# scheme.net
KiCad netlist of a schematic drawn in Altium Designer
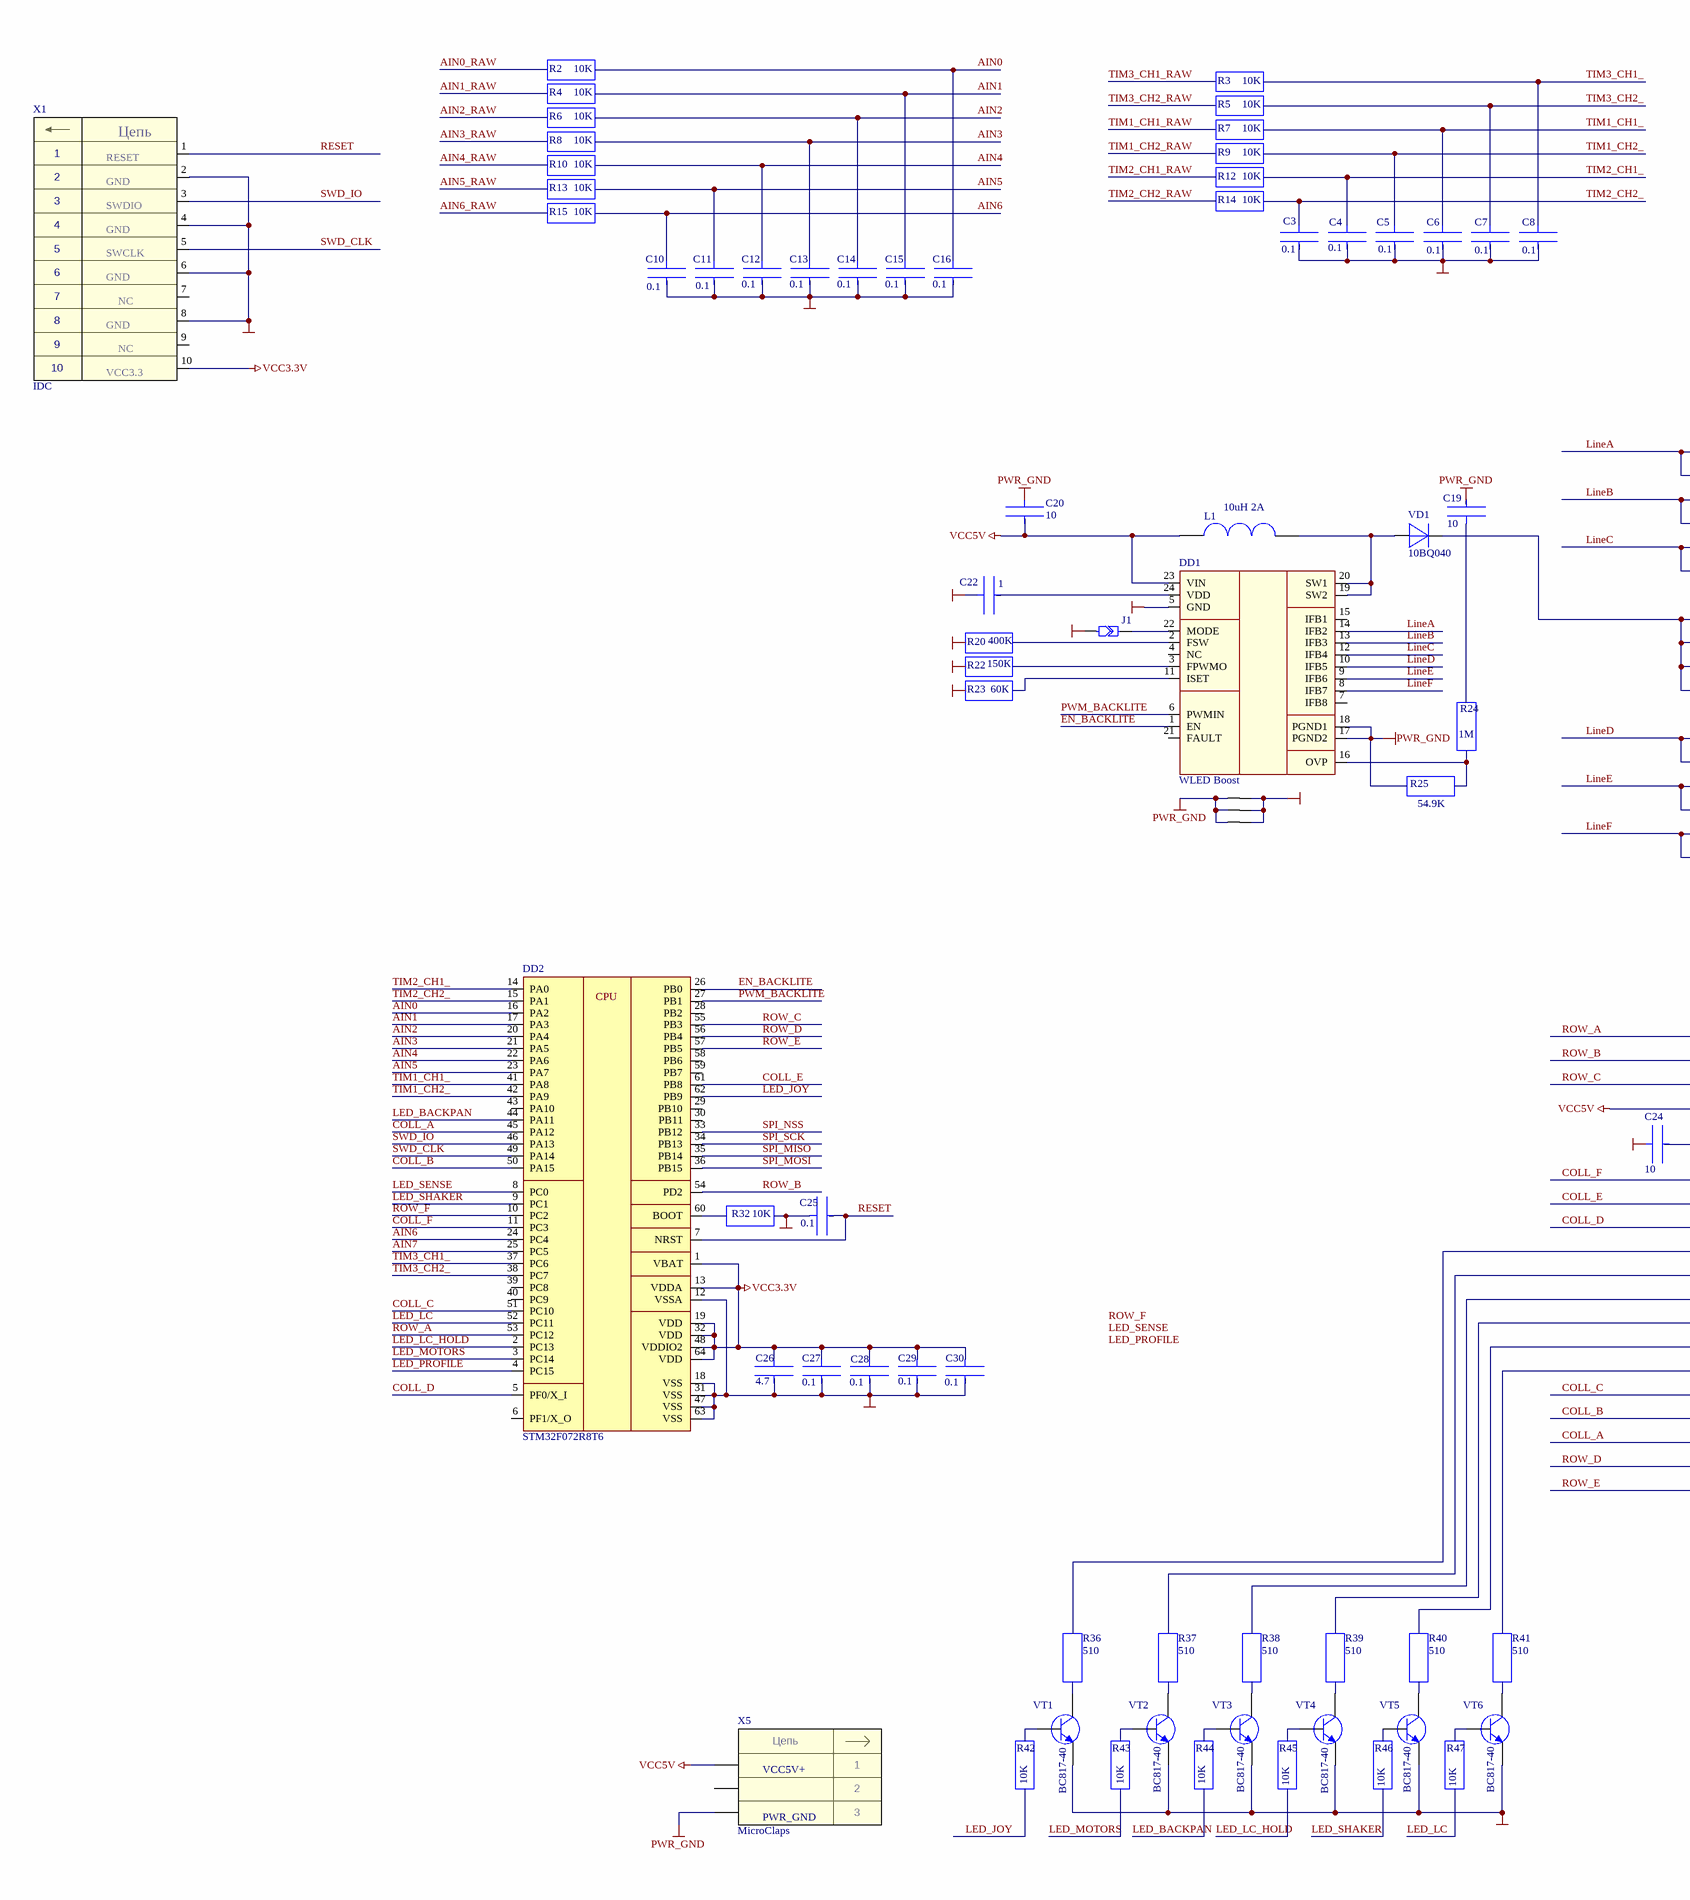
[diagram p0: scheme.SchDoc, left]
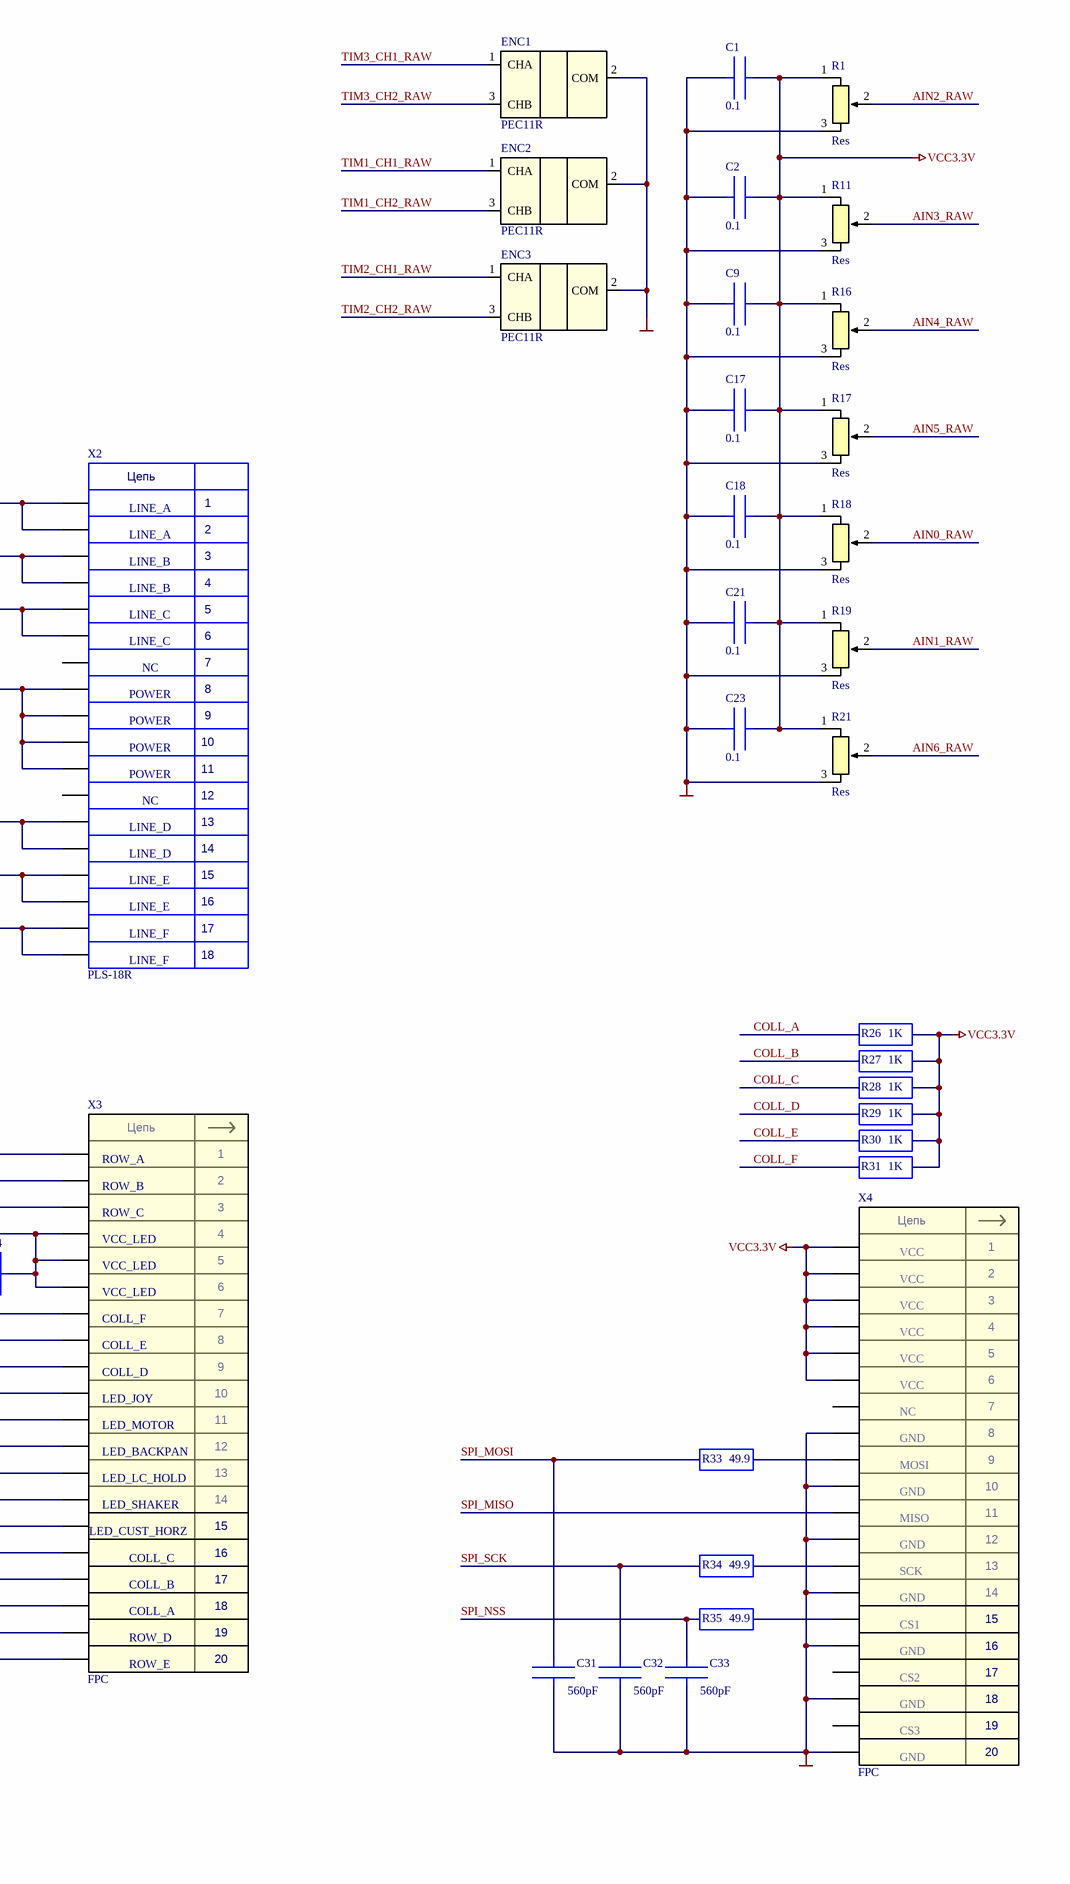
[diagram p1: scheme.SchDoc, right]

(export (version "E")
  (design (tool "Eeschema 10.0.6"))
  (components
    (comp (ref "1")
      (value "Wire Bridge")
      (footprint "Bridge 1.2mm")
      (libsource (lib "DiscreteDevicesCommon") (part "Wire Bridge"))
    )
    (comp (ref "2")
      (value "Wire Bridge")
      (footprint "Bridge 1.2mm")
      (libsource (lib "DiscreteDevicesCommon") (part "Wire Bridge"))
    )
    (comp (ref "3")
      (value "Wire Bridge")
      (footprint "Bridge 1.2mm")
      (libsource (lib "DiscreteDevicesCommon") (part "Wire Bridge"))
    )
    (comp (ref "C1")
      (value "0.1")
      (footprint "C0402")
      (description "Capacitor")
      (fields (field (name "VOLTAGE") "16") (field (name "Comment") "Cap"))
      (libsource (lib "DiscreteDevicesCommon") (part "Cap"))
    )
    (comp (ref "C2")
      (value "0.1")
      (footprint "C0402")
      (description "Capacitor")
      (fields (field (name "VOLTAGE") "16") (field (name "Comment") "Cap"))
      (libsource (lib "DiscreteDevicesCommon") (part "Cap"))
    )
    (comp (ref "C3")
      (value "0.1")
      (footprint "C0402")
      (description "Capacitor")
      (fields (field (name "VOLTAGE") "16") (field (name "Comment") "Cap"))
      (libsource (lib "DiscreteDevicesCommon") (part "Cap"))
    )
    (comp (ref "C4")
      (value "0.1")
      (footprint "C0402")
      (description "Capacitor")
      (fields (field (name "VOLTAGE") "16") (field (name "Comment") "Cap"))
      (libsource (lib "DiscreteDevicesCommon") (part "Cap"))
    )
    (comp (ref "C5")
      (value "0.1")
      (footprint "C0402")
      (description "Capacitor")
      (fields (field (name "VOLTAGE") "16") (field (name "Comment") "Cap"))
      (libsource (lib "DiscreteDevicesCommon") (part "Cap"))
    )
    (comp (ref "C6")
      (value "0.1")
      (footprint "C0402")
      (description "Capacitor")
      (fields (field (name "VOLTAGE") "16") (field (name "Comment") "Cap"))
      (libsource (lib "DiscreteDevicesCommon") (part "Cap"))
    )
    (comp (ref "C7")
      (value "0.1")
      (footprint "C0402")
      (description "Capacitor")
      (fields (field (name "VOLTAGE") "16") (field (name "Comment") "Cap"))
      (libsource (lib "DiscreteDevicesCommon") (part "Cap"))
    )
    (comp (ref "C8")
      (value "0.1")
      (footprint "C0402")
      (description "Capacitor")
      (fields (field (name "VOLTAGE") "16") (field (name "Comment") "Cap"))
      (libsource (lib "DiscreteDevicesCommon") (part "Cap"))
    )
    (comp (ref "C9")
      (value "0.1")
      (footprint "C0402")
      (description "Capacitor")
      (fields (field (name "VOLTAGE") "16") (field (name "Comment") "Cap"))
      (libsource (lib "DiscreteDevicesCommon") (part "Cap"))
    )
    (comp (ref "C10")
      (value "0.1")
      (footprint "C0402")
      (description "Capacitor")
      (fields (field (name "VOLTAGE") "16") (field (name "Comment") "Cap"))
      (libsource (lib "DiscreteDevicesCommon") (part "Cap"))
    )
    (comp (ref "C11")
      (value "0.1")
      (footprint "C0402")
      (description "Capacitor")
      (fields (field (name "VOLTAGE") "16") (field (name "Comment") "Cap"))
      (libsource (lib "DiscreteDevicesCommon") (part "Cap"))
    )
    (comp (ref "C12")
      (value "0.1")
      (footprint "C0402")
      (description "Capacitor")
      (fields (field (name "VOLTAGE") "16") (field (name "Comment") "Cap"))
      (libsource (lib "DiscreteDevicesCommon") (part "Cap"))
    )
    (comp (ref "C13")
      (value "0.1")
      (footprint "C0402")
      (description "Capacitor")
      (fields (field (name "VOLTAGE") "16") (field (name "Comment") "Cap"))
      (libsource (lib "DiscreteDevicesCommon") (part "Cap"))
    )
    (comp (ref "C14")
      (value "0.1")
      (footprint "C0402")
      (description "Capacitor")
      (fields (field (name "VOLTAGE") "16") (field (name "Comment") "Cap"))
      (libsource (lib "DiscreteDevicesCommon") (part "Cap"))
    )
    (comp (ref "C15")
      (value "0.1")
      (footprint "C0402")
      (description "Capacitor")
      (fields (field (name "VOLTAGE") "16") (field (name "Comment") "Cap"))
      (libsource (lib "DiscreteDevicesCommon") (part "Cap"))
    )
    (comp (ref "C16")
      (value "0.1")
      (footprint "C0402")
      (description "Capacitor")
      (fields (field (name "VOLTAGE") "16") (field (name "Comment") "Cap"))
      (libsource (lib "DiscreteDevicesCommon") (part "Cap"))
    )
    (comp (ref "C17")
      (value "0.1")
      (footprint "C0402")
      (description "Capacitor")
      (fields (field (name "VOLTAGE") "16") (field (name "Comment") "Cap"))
      (libsource (lib "DiscreteDevicesCommon") (part "Cap"))
    )
    (comp (ref "C18")
      (value "0.1")
      (footprint "C0402")
      (description "Capacitor")
      (fields (field (name "VOLTAGE") "16") (field (name "Comment") "Cap"))
      (libsource (lib "DiscreteDevicesCommon") (part "Cap"))
    )
    (comp (ref "C19")
      (value "10")
      (footprint "C1206")
      (description "Capacitor")
      (fields (field (name "VOLTAGE") "25") (field (name "Comment") "Cap"))
      (libsource (lib "DiscreteDevicesCommon") (part "Cap"))
    )
    (comp (ref "C20")
      (value "10")
      (footprint "C1206")
      (description "Capacitor")
      (fields (field (name "VOLTAGE") "25") (field (name "Comment") "Cap"))
      (libsource (lib "DiscreteDevicesCommon") (part "Cap"))
    )
    (comp (ref "C21")
      (value "0.1")
      (footprint "C0402")
      (description "Capacitor")
      (fields (field (name "VOLTAGE") "16") (field (name "Comment") "Cap"))
      (libsource (lib "DiscreteDevicesCommon") (part "Cap"))
    )
    (comp (ref "C22")
      (value "1")
      (footprint "C0603")
      (description "Capacitor")
      (fields (field (name "VOLTAGE") "6.3") (field (name "Comment") "Cap"))
      (libsource (lib "DiscreteDevicesCommon") (part "Cap"))
    )
    (comp (ref "C23")
      (value "0.1")
      (footprint "C0402")
      (description "Capacitor")
      (fields (field (name "VOLTAGE") "16") (field (name "Comment") "Cap"))
      (libsource (lib "DiscreteDevicesCommon") (part "Cap"))
    )
    (comp (ref "C24")
      (value "10")
      (footprint "C1206")
      (description "Capacitor")
      (fields (field (name "VOLTAGE") "25") (field (name "Comment") "Cap"))
      (libsource (lib "DiscreteDevicesCommon") (part "Cap"))
    )
    (comp (ref "C25")
      (value "0.1")
      (footprint "C0402")
      (description "Capacitor")
      (fields (field (name "VOLTAGE") "16") (field (name "Comment") "Cap"))
      (libsource (lib "DiscreteDevicesCommon") (part "Cap"))
    )
    (comp (ref "C26")
      (value "4.7")
      (footprint "C0402")
      (description "Capacitor")
      (fields (field (name "VOLTAGE") "6.3") (field (name "Comment") "Cap"))
      (libsource (lib "DiscreteDevicesCommon") (part "Cap"))
    )
    (comp (ref "C27")
      (value "0.1")
      (footprint "C0402")
      (description "Capacitor")
      (fields (field (name "VOLTAGE") "16") (field (name "Comment") "Cap"))
      (libsource (lib "DiscreteDevicesCommon") (part "Cap"))
    )
    (comp (ref "C28")
      (value "0.1")
      (footprint "C0402")
      (description "Capacitor")
      (fields (field (name "VOLTAGE") "16") (field (name "Comment") "Cap"))
      (libsource (lib "DiscreteDevicesCommon") (part "Cap"))
    )
    (comp (ref "C29")
      (value "0.1")
      (footprint "C0402")
      (description "Capacitor")
      (fields (field (name "VOLTAGE") "16") (field (name "Comment") "Cap"))
      (libsource (lib "DiscreteDevicesCommon") (part "Cap"))
    )
    (comp (ref "C30")
      (value "0.1")
      (footprint "C0402")
      (description "Capacitor")
      (fields (field (name "VOLTAGE") "16") (field (name "Comment") "Cap"))
      (libsource (lib "DiscreteDevicesCommon") (part "Cap"))
    )
    (comp (ref "C31")
      (value "560pF")
      (footprint "C0402")
      (description "Capacitor")
      (fields (field (name "VOLTAGE") "16") (field (name "Comment") "Cap"))
      (libsource (lib "DiscreteDevicesCommon") (part "Cap"))
    )
    (comp (ref "C32")
      (value "560pF")
      (footprint "C0402")
      (description "Capacitor")
      (fields (field (name "VOLTAGE") "16") (field (name "Comment") "Cap"))
      (libsource (lib "DiscreteDevicesCommon") (part "Cap"))
    )
    (comp (ref "C33")
      (value "560pF")
      (footprint "C0402")
      (description "Capacitor")
      (fields (field (name "VOLTAGE") "16") (field (name "Comment") "Cap"))
      (libsource (lib "DiscreteDevicesCommon") (part "Cap"))
    )
    (comp (ref "DD1")
      (value "WLED Boost")
      (footprint "WQFN-24")
      (libsource (lib "ChipsCommon") (part "TPS61185"))
    )
    (comp (ref "DD2")
      (value "STM32F072Rx")
      (footprint "LQFP64_M")
      (fields (field (name "TYPE") "STM32F072R8T6"))
      (libsource (lib "ChipsCommon") (part "STM32F072Rx"))
    )
    (comp (ref "ENC1")
      (value "PEC11R")
      (footprint "PEC11R")
      (description "ENCODER")
      (libsource (lib "DiscreteDevicesCommon") (part "PEC11R ENCODER"))
    )
    (comp (ref "ENC2")
      (value "PEC11R")
      (footprint "PEC11R")
      (description "ENCODER")
      (libsource (lib "DiscreteDevicesCommon") (part "PEC11R ENCODER"))
    )
    (comp (ref "ENC3")
      (value "PEC11R")
      (footprint "PEC11R")
      (description "ENCODER")
      (libsource (lib "DiscreteDevicesCommon") (part "PEC11R ENCODER"))
    )
    (comp (ref "J1")
      (value "JumperB")
      (footprint "SM/JUMPER_SHORT")
      (description "Jumper on Board")
      (libsource (lib "ConnectorsCommon") (part "JumperB"))
    )
    (comp (ref "L1")
      (value "10uH 2A")
      (footprint "SDR0805")
      (description "Inductor")
      (fields (field (name "Comment") "IND2"))
      (libsource (lib "DiscreteDevicesCommon") (part "IND2"))
    )
    (comp (ref "R1")
      (value "Res")
      (footprint "P16NP_16mm")
      (description "Potenciometr")
      (libsource (lib "DiscreteDevicesCommon") (part "P16A Res"))
    )
    (comp (ref "R2")
      (value "10K")
      (footprint "R0402")
      (description "Resistor")
      (fields (field (name "Comment") "Res"))
      (libsource (lib "") (part "Res_1"))
    )
    (comp (ref "R3")
      (value "10K")
      (footprint "R0402")
      (description "Resistor")
      (fields (field (name "Comment") "Res"))
      (libsource (lib "") (part "Res_1"))
    )
    (comp (ref "R4")
      (value "10K")
      (footprint "R0402")
      (description "Resistor")
      (fields (field (name "Comment") "Res"))
      (libsource (lib "") (part "Res_1"))
    )
    (comp (ref "R5")
      (value "10K")
      (footprint "R0402")
      (description "Resistor")
      (fields (field (name "Comment") "Res"))
      (libsource (lib "") (part "Res_1"))
    )
    (comp (ref "R6")
      (value "10K")
      (footprint "R0402")
      (description "Resistor")
      (fields (field (name "Comment") "Res"))
      (libsource (lib "") (part "Res_1"))
    )
    (comp (ref "R7")
      (value "10K")
      (footprint "R0402")
      (description "Resistor")
      (fields (field (name "Comment") "Res"))
      (libsource (lib "") (part "Res_1"))
    )
    (comp (ref "R8")
      (value "10K")
      (footprint "R0402")
      (description "Resistor")
      (fields (field (name "Comment") "Res"))
      (libsource (lib "") (part "Res_1"))
    )
    (comp (ref "R9")
      (value "10K")
      (footprint "R0402")
      (description "Resistor")
      (fields (field (name "Comment") "Res"))
      (libsource (lib "") (part "Res_1"))
    )
    (comp (ref "R10")
      (value "10K")
      (footprint "R0402")
      (description "Resistor")
      (fields (field (name "Comment") "Res"))
      (libsource (lib "") (part "Res_1"))
    )
    (comp (ref "R11")
      (value "Res")
      (footprint "P16NP_16mm")
      (description "Potenciometr")
      (libsource (lib "DiscreteDevicesCommon") (part "P16A Res"))
    )
    (comp (ref "R12")
      (value "10K")
      (footprint "R0402")
      (description "Resistor")
      (fields (field (name "Comment") "Res"))
      (libsource (lib "") (part "Res_1"))
    )
    (comp (ref "R13")
      (value "10K")
      (footprint "R0402")
      (description "Resistor")
      (fields (field (name "Comment") "Res"))
      (libsource (lib "") (part "Res_1"))
    )
    (comp (ref "R14")
      (value "10K")
      (footprint "R0402")
      (description "Resistor")
      (fields (field (name "Comment") "Res"))
      (libsource (lib "") (part "Res_1"))
    )
    (comp (ref "R15")
      (value "10K")
      (footprint "R0402")
      (description "Resistor")
      (fields (field (name "Comment") "Res"))
      (libsource (lib "") (part "Res_1"))
    )
    (comp (ref "R16")
      (value "Res")
      (footprint "P16NP_16mm")
      (description "Potenciometr")
      (libsource (lib "DiscreteDevicesCommon") (part "P16A Res"))
    )
    (comp (ref "R17")
      (value "Res")
      (footprint "P16NP_16mm")
      (description "Potenciometr")
      (libsource (lib "DiscreteDevicesCommon") (part "P16A Res"))
    )
    (comp (ref "R18")
      (value "Res")
      (footprint "P16NP_16mm")
      (description "Potenciometr")
      (libsource (lib "DiscreteDevicesCommon") (part "P16A Res"))
    )
    (comp (ref "R19")
      (value "Res")
      (footprint "P16NP_16mm")
      (description "Potenciometr")
      (libsource (lib "DiscreteDevicesCommon") (part "P16A Res"))
    )
    (comp (ref "R20")
      (value "400K")
      (footprint "R0402")
      (description "Resistor")
      (fields (field (name "Comment") "Res"))
      (libsource (lib "") (part "Res_1"))
    )
    (comp (ref "R21")
      (value "Res")
      (footprint "P16NP_16mm")
      (description "Potenciometr")
      (libsource (lib "DiscreteDevicesCommon") (part "P16A Res"))
    )
    (comp (ref "R22")
      (value "150К")
      (footprint "R0402")
      (description "Resistor")
      (fields (field (name "Comment") "Res"))
      (libsource (lib "") (part "Res_1"))
    )
    (comp (ref "R23")
      (value "60К")
      (footprint "R0402")
      (description "Resistor")
      (fields (field (name "Comment") "Res"))
      (libsource (lib "") (part "Res_1"))
    )
    (comp (ref "R24")
      (value "1M")
      (footprint "R0603")
      (description "Resistor")
      (fields (field (name "Comment") "Res"))
      (libsource (lib "DiscreteDevicesCommon") (part "Res"))
    )
    (comp (ref "R25")
      (value "54.9K")
      (footprint "R0603")
      (description "Resistor")
      (fields (field (name "Comment") "Res"))
      (libsource (lib "") (part "Res_2"))
    )
    (comp (ref "R26")
      (value "1K")
      (footprint "R0402")
      (description "Resistor")
      (fields (field (name "Comment") "Res"))
      (libsource (lib "") (part "Res_1"))
    )
    (comp (ref "R27")
      (value "1K")
      (footprint "R0402")
      (description "Resistor")
      (fields (field (name "Comment") "Res"))
      (libsource (lib "") (part "Res_1"))
    )
    (comp (ref "R28")
      (value "1K")
      (footprint "R0402")
      (description "Resistor")
      (fields (field (name "Comment") "Res"))
      (libsource (lib "") (part "Res_1"))
    )
    (comp (ref "R29")
      (value "1K")
      (footprint "R0402")
      (description "Resistor")
      (fields (field (name "Comment") "Res"))
      (libsource (lib "") (part "Res_1"))
    )
    (comp (ref "R30")
      (value "1K")
      (footprint "R0402")
      (description "Resistor")
      (fields (field (name "Comment") "Res"))
      (libsource (lib "") (part "Res_1"))
    )
    (comp (ref "R31")
      (value "1K")
      (footprint "R0402")
      (description "Resistor")
      (fields (field (name "Comment") "Res"))
      (libsource (lib "") (part "Res_1"))
    )
    (comp (ref "R32")
      (value "10K")
      (footprint "R0402")
      (description "Resistor")
      (fields (field (name "Comment") "Res"))
      (libsource (lib "") (part "Res_1"))
    )
    (comp (ref "R33")
      (value "49.9")
      (footprint "R0402")
      (description "Resistor")
      (fields (field (name "Comment") "Res"))
      (libsource (lib "") (part "Res_1"))
    )
    (comp (ref "R34")
      (value "49.9")
      (footprint "R0402")
      (description "Resistor")
      (fields (field (name "Comment") "Res"))
      (libsource (lib "") (part "Res_1"))
    )
    (comp (ref "R35")
      (value "49.9")
      (footprint "R0402")
      (description "Resistor")
      (fields (field (name "Comment") "Res"))
      (libsource (lib "") (part "Res_1"))
    )
    (comp (ref "R36")
      (value "510")
      (footprint "R0402")
      (description "Resistor")
      (fields (field (name "Comment") "Res"))
      (libsource (lib "DiscreteDevicesCommon") (part "Res"))
    )
    (comp (ref "R37")
      (value "510")
      (footprint "R0402")
      (description "Resistor")
      (fields (field (name "Comment") "Res"))
      (libsource (lib "DiscreteDevicesCommon") (part "Res"))
    )
    (comp (ref "R38")
      (value "510")
      (footprint "R0402")
      (description "Resistor")
      (fields (field (name "Comment") "Res"))
      (libsource (lib "DiscreteDevicesCommon") (part "Res"))
    )
    (comp (ref "R39")
      (value "510")
      (footprint "R0402")
      (description "Resistor")
      (fields (field (name "Comment") "Res"))
      (libsource (lib "DiscreteDevicesCommon") (part "Res"))
    )
    (comp (ref "R40")
      (value "510")
      (footprint "R0402")
      (description "Resistor")
      (fields (field (name "Comment") "Res"))
      (libsource (lib "DiscreteDevicesCommon") (part "Res"))
    )
    (comp (ref "R41")
      (value "510")
      (footprint "R0402")
      (description "Resistor")
      (fields (field (name "Comment") "Res"))
      (libsource (lib "DiscreteDevicesCommon") (part "Res"))
    )
    (comp (ref "R42")
      (value "10K")
      (footprint "R0402")
      (description "Resistor")
      (fields (field (name "Comment") "Res"))
      (libsource (lib "DiscreteDevicesCommon") (part "Res"))
    )
    (comp (ref "R43")
      (value "10K")
      (footprint "R0402")
      (description "Resistor")
      (fields (field (name "Comment") "Res"))
      (libsource (lib "DiscreteDevicesCommon") (part "Res"))
    )
    (comp (ref "R44")
      (value "10K")
      (footprint "R0402")
      (description "Resistor")
      (fields (field (name "Comment") "Res"))
      (libsource (lib "DiscreteDevicesCommon") (part "Res"))
    )
    (comp (ref "R45")
      (value "10K")
      (footprint "R0402")
      (description "Resistor")
      (fields (field (name "Comment") "Res"))
      (libsource (lib "DiscreteDevicesCommon") (part "Res"))
    )
    (comp (ref "R46")
      (value "10K")
      (footprint "R0402")
      (description "Resistor")
      (fields (field (name "Comment") "Res"))
      (libsource (lib "DiscreteDevicesCommon") (part "Res"))
    )
    (comp (ref "R47")
      (value "10K")
      (footprint "R0402")
      (description "Resistor")
      (fields (field (name "Comment") "Res"))
      (libsource (lib "DiscreteDevicesCommon") (part "Res"))
    )
    (comp (ref "VD1")
      (value "Diode")
      (footprint "DI-SMB")
      (fields (field (name "TYPE") "10BQ040"))
      (libsource (lib "DiscreteDevicesCommon") (part "Diode"))
    )
    (comp (ref "VT1")
      (value "Transistor NPN")
      (footprint "SOT23-3L")
      (description "NPN transistor")
      (fields (field (name "TYPE") "BC817-40"))
      (libsource (lib "DiscreteDevicesCommon") (part "Trans NPN"))
    )
    (comp (ref "VT2")
      (value "Transistor NPN")
      (footprint "SOT23-3L")
      (description "NPN transistor")
      (fields (field (name "TYPE") "BC817-40"))
      (libsource (lib "DiscreteDevicesCommon") (part "Trans NPN"))
    )
    (comp (ref "VT3")
      (value "Transistor NPN")
      (footprint "SOT23-3L")
      (description "NPN transistor")
      (fields (field (name "TYPE") "BC817-40"))
      (libsource (lib "DiscreteDevicesCommon") (part "Trans NPN"))
    )
    (comp (ref "VT4")
      (value "Transistor NPN")
      (footprint "SOT23-3L")
      (description "NPN transistor")
      (fields (field (name "TYPE") "BC817-40"))
      (libsource (lib "DiscreteDevicesCommon") (part "Trans NPN"))
    )
    (comp (ref "VT5")
      (value "Transistor NPN")
      (footprint "SOT23-3L")
      (description "NPN transistor")
      (fields (field (name "TYPE") "BC817-40"))
      (libsource (lib "DiscreteDevicesCommon") (part "Trans NPN"))
    )
    (comp (ref "VT6")
      (value "Transistor NPN")
      (footprint "SOT23-3L")
      (description "NPN transistor")
      (fields (field (name "TYPE") "BC817-40"))
      (libsource (lib "DiscreteDevicesCommon") (part "Trans NPN"))
    )
    (comp (ref "X1")
      (value "IDC")
      (footprint "IDC2-10MS-SMD")
      (description "IDC 2mm 10 pin")
      (libsource (lib "ConnectorsCommon") (part "IDC2-10"))
    )
    (comp (ref "X2")
      (value "18-pin Out")
      (footprint "PLS-18R")
      (description "18-pin Out Connector")
      (fields (field (name "TYPE") "PLS-18R"))
      (libsource (lib "ConnectorsCommon") (part "18-pin Out"))
    )
    (comp (ref "X3")
      (value "FPC")
      (footprint "FPC-20 TE 2-84953-0")
      (description "FPC 20pin 1mm")
      (libsource (lib "ConnectorsCommon") (part "FPC-20pin 1mm"))
    )
    (comp (ref "X4")
      (value "FPC")
      (footprint "FPC-20 TE 2-1734592-0")
      (description "FPC 20pin 0.5mm")
      (libsource (lib "ConnectorsCommon") (part "FPC-20pin 0.5mm"))
    )
    (comp (ref "X5")
      (value "MicroClaps")
      (footprint "MicroClaspSingle - 3Pin")
      (description "MicroClapsConnector 3Pin SingleLine")
      (libsource (lib "ConnectorsCommon") (part "MicroClapsSingle-3"))
    )
  )
  (nets
    (net (code "1") (name "/AIN0") (class "Default")
      (node (ref "C16") (pin "1") (pinfunction "1_1") (pintype "passive"))
      (node (ref "DD2") (pin "16") (pinfunction "PA2_16") (pintype "passive"))
      (node (ref "R2") (pin "2") (pinfunction "2_2") (pintype "passive"))
    )
    (net (code "2") (name "/AIN0_RAW") (class "Default")
      (node (ref "R18") (pin "2") (pinfunction "2_2") (pintype "passive"))
      (node (ref "R2") (pin "1") (pinfunction "1_1") (pintype "passive"))
    )
    (net (code "3") (name "/AIN1") (class "Default")
      (node (ref "C15") (pin "1") (pinfunction "1_1") (pintype "passive"))
      (node (ref "DD2") (pin "17") (pinfunction "PA3_17") (pintype "passive"))
      (node (ref "R4") (pin "2") (pinfunction "2_2") (pintype "passive"))
    )
    (net (code "4") (name "/AIN1_RAW") (class "Default")
      (node (ref "R19") (pin "2") (pinfunction "2_2") (pintype "passive"))
      (node (ref "R4") (pin "1") (pinfunction "1_1") (pintype "passive"))
    )
    (net (code "5") (name "/AIN2") (class "Default")
      (node (ref "C14") (pin "1") (pinfunction "1_1") (pintype "passive"))
      (node (ref "DD2") (pin "20") (pinfunction "PA4_20") (pintype "passive"))
      (node (ref "R6") (pin "2") (pinfunction "2_2") (pintype "passive"))
    )
    (net (code "6") (name "/AIN2_RAW") (class "Default")
      (node (ref "R1") (pin "2") (pinfunction "2_2") (pintype "passive"))
      (node (ref "R6") (pin "1") (pinfunction "1_1") (pintype "passive"))
    )
    (net (code "7") (name "/AIN3") (class "Default")
      (node (ref "C13") (pin "1") (pinfunction "1_1") (pintype "passive"))
      (node (ref "DD2") (pin "21") (pinfunction "PA5_21") (pintype "passive"))
      (node (ref "R8") (pin "2") (pinfunction "2_2") (pintype "passive"))
    )
    (net (code "8") (name "/AIN3_RAW") (class "Default")
      (node (ref "R11") (pin "2") (pinfunction "2_2") (pintype "passive"))
      (node (ref "R8") (pin "1") (pinfunction "1_1") (pintype "passive"))
    )
    (net (code "9") (name "/AIN4") (class "Default")
      (node (ref "C12") (pin "1") (pinfunction "1_1") (pintype "passive"))
      (node (ref "DD2") (pin "22") (pinfunction "PA6_22") (pintype "passive"))
      (node (ref "R10") (pin "2") (pinfunction "2_2") (pintype "passive"))
    )
    (net (code "10") (name "/AIN4_RAW") (class "Default")
      (node (ref "R10") (pin "1") (pinfunction "1_1") (pintype "passive"))
      (node (ref "R16") (pin "2") (pinfunction "2_2") (pintype "passive"))
    )
    (net (code "11") (name "/AIN5") (class "Default")
      (node (ref "C11") (pin "1") (pinfunction "1_1") (pintype "passive"))
      (node (ref "DD2") (pin "23") (pinfunction "PA7_23") (pintype "passive"))
      (node (ref "R13") (pin "2") (pinfunction "2_2") (pintype "passive"))
    )
    (net (code "12") (name "/AIN5_RAW") (class "Default")
      (node (ref "R13") (pin "1") (pinfunction "1_1") (pintype "passive"))
      (node (ref "R17") (pin "2") (pinfunction "2_2") (pintype "passive"))
    )
    (net (code "13") (name "/AIN6") (class "Default")
      (node (ref "C10") (pin "1") (pinfunction "1_1") (pintype "passive"))
      (node (ref "DD2") (pin "24") (pinfunction "PC4_24") (pintype "passive"))
      (node (ref "R15") (pin "2") (pinfunction "2_2") (pintype "passive"))
    )
    (net (code "14") (name "/AIN6_RAW") (class "Default")
      (node (ref "R15") (pin "1") (pinfunction "1_1") (pintype "passive"))
      (node (ref "R21") (pin "2") (pinfunction "2_2") (pintype "passive"))
    )
    (net (code "15") (name "/AIN7") (class "Default")
      (node (ref "DD2") (pin "25") (pinfunction "PC5_25") (pintype "passive"))
    )
    (net (code "16") (name "/COLL_A") (class "Default")
      (node (ref "DD2") (pin "45") (pinfunction "PA12_45") (pintype "passive"))
      (node (ref "R26") (pin "1") (pinfunction "1_1") (pintype "passive"))
      (node (ref "X3") (pin "18") (pinfunction "XXX_18") (pintype "passive"))
    )
    (net (code "17") (name "/COLL_B") (class "Default")
      (node (ref "DD2") (pin "50") (pinfunction "PA15_50") (pintype "passive"))
      (node (ref "R27") (pin "1") (pinfunction "1_1") (pintype "passive"))
      (node (ref "X3") (pin "17") (pinfunction "XXX_17") (pintype "passive"))
    )
    (net (code "18") (name "/COLL_C") (class "Default")
      (node (ref "DD2") (pin "51") (pinfunction "PC10_51") (pintype "passive"))
      (node (ref "R28") (pin "1") (pinfunction "1_1") (pintype "passive"))
      (node (ref "X3") (pin "16") (pinfunction "XXX_16") (pintype "passive"))
    )
    (net (code "19") (name "/COLL_D") (class "Default")
      (node (ref "DD2") (pin "5") (pinfunction "PF0/X_I_5") (pintype "passive"))
      (node (ref "R29") (pin "1") (pinfunction "1_1") (pintype "passive"))
      (node (ref "X3") (pin "9") (pinfunction "XXX_9") (pintype "passive"))
    )
    (net (code "20") (name "/COLL_E") (class "Default")
      (node (ref "DD2") (pin "61") (pinfunction "PB8_61") (pintype "passive"))
      (node (ref "R30") (pin "1") (pinfunction "1_1") (pintype "passive"))
      (node (ref "X3") (pin "8") (pinfunction "XXX_8") (pintype "passive"))
    )
    (net (code "21") (name "/COLL_F") (class "Default")
      (node (ref "DD2") (pin "11") (pinfunction "PC3_11") (pintype "passive"))
      (node (ref "R31") (pin "1") (pinfunction "1_1") (pintype "passive"))
      (node (ref "X3") (pin "7") (pinfunction "XXX_7") (pintype "passive"))
    )
    (net (code "22") (name "/EN_BACKLITE") (class "Default")
      (node (ref "DD1") (pin "1") (pinfunction "EN_1") (pintype "passive"))
      (node (ref "DD2") (pin "26") (pinfunction "PB0_26") (pintype "passive"))
    )
    (net (code "23") (name "/LED_BACKPAN") (class "Default")
      (node (ref "DD2") (pin "44") (pinfunction "PA11_44") (pintype "passive"))
      (node (ref "R44") (pin "1") (pinfunction "1_1") (pintype "passive"))
    )
    (net (code "24") (name "/LED_JOY") (class "Default")
      (node (ref "DD2") (pin "62") (pinfunction "PB9_62") (pintype "passive"))
      (node (ref "R42") (pin "1") (pinfunction "1_1") (pintype "passive"))
    )
    (net (code "25") (name "/LED_LC") (class "Default")
      (node (ref "DD2") (pin "52") (pinfunction "PC11_52") (pintype "passive"))
      (node (ref "R47") (pin "1") (pinfunction "1_1") (pintype "passive"))
    )
    (net (code "26") (name "/LED_LC_HOLD") (class "Default")
      (node (ref "DD2") (pin "2") (pinfunction "PC13_2") (pintype "passive"))
      (node (ref "R45") (pin "1") (pinfunction "1_1") (pintype "passive"))
    )
    (net (code "27") (name "/LED_MOTORS") (class "Default")
      (node (ref "DD2") (pin "3") (pinfunction "PC14_3") (pintype "passive"))
      (node (ref "R43") (pin "1") (pinfunction "1_1") (pintype "passive"))
    )
    (net (code "28") (name "/LED_PROFILE") (class "Default")
      (node (ref "DD2") (pin "4") (pinfunction "PC15_4") (pintype "passive"))
    )
    (net (code "29") (name "/LED_SENSE") (class "Default")
      (node (ref "DD2") (pin "8") (pinfunction "PC0_8") (pintype "passive"))
    )
    (net (code "30") (name "/LED_SHAKER") (class "Default")
      (node (ref "DD2") (pin "9") (pinfunction "PC1_9") (pintype "passive"))
      (node (ref "R46") (pin "1") (pinfunction "1_1") (pintype "passive"))
    )
    (net (code "31") (name "/LineA") (class "Default")
      (node (ref "DD1") (pin "14") (pinfunction "IFB2_14") (pintype "passive"))
      (node (ref "X2") (pin "1") (pinfunction "XXX_1") (pintype "passive"))
      (node (ref "X2") (pin "2") (pinfunction "XXX_2") (pintype "passive"))
    )
    (net (code "32") (name "/LineB") (class "Default")
      (node (ref "DD1") (pin "13") (pinfunction "IFB3_13") (pintype "passive"))
      (node (ref "X2") (pin "3") (pinfunction "XXX_3") (pintype "passive"))
      (node (ref "X2") (pin "4") (pinfunction "XXX_4") (pintype "passive"))
    )
    (net (code "33") (name "/LineC") (class "Default")
      (node (ref "DD1") (pin "12") (pinfunction "IFB4_12") (pintype "passive"))
      (node (ref "X2") (pin "5") (pinfunction "XXX_5") (pintype "passive"))
      (node (ref "X2") (pin "6") (pinfunction "XXX_6") (pintype "passive"))
    )
    (net (code "34") (name "/LineD") (class "Default")
      (node (ref "DD1") (pin "10") (pinfunction "IFB5_10") (pintype "passive"))
      (node (ref "X2") (pin "13") (pinfunction "XXX_13") (pintype "passive"))
      (node (ref "X2") (pin "14") (pinfunction "XXX_14") (pintype "passive"))
    )
    (net (code "35") (name "/LineE") (class "Default")
      (node (ref "DD1") (pin "9") (pinfunction "IFB6_9") (pintype "passive"))
      (node (ref "X2") (pin "15") (pinfunction "XXX_15") (pintype "passive"))
      (node (ref "X2") (pin "16") (pinfunction "XXX_16") (pintype "passive"))
    )
    (net (code "36") (name "/LineF") (class "Default")
      (node (ref "DD1") (pin "8") (pinfunction "IFB7_8") (pintype "passive"))
      (node (ref "X2") (pin "17") (pinfunction "XXX_17") (pintype "passive"))
      (node (ref "X2") (pin "18") (pinfunction "XXX_18") (pintype "passive"))
    )
    (net (code "37") (name "/PWM_BACKLITE") (class "Default")
      (node (ref "DD1") (pin "6") (pinfunction "PWMIN_6") (pintype "passive"))
      (node (ref "DD2") (pin "27") (pinfunction "PB1_27") (pintype "passive"))
    )
    (net (code "38") (name "/RESET") (class "Default")
      (node (ref "C25") (pin "2") (pinfunction "2_2") (pintype "passive"))
      (node (ref "DD2") (pin "7") (pinfunction "NRST_7") (pintype "passive"))
      (node (ref "X1") (pin "1") (pinfunction "1_1") (pintype "passive"))
    )
    (net (code "39") (name "/ROW_A") (class "Default")
      (node (ref "DD2") (pin "53") (pinfunction "PC12_53") (pintype "passive"))
      (node (ref "X3") (pin "1") (pinfunction "XXX_1") (pintype "passive"))
    )
    (net (code "40") (name "/ROW_B") (class "Default")
      (node (ref "DD2") (pin "54") (pinfunction "PD2_54") (pintype "passive"))
      (node (ref "X3") (pin "2") (pinfunction "XXX_2") (pintype "passive"))
    )
    (net (code "41") (name "/ROW_C") (class "Default")
      (node (ref "DD2") (pin "55") (pinfunction "PB3_55") (pintype "passive"))
      (node (ref "X3") (pin "3") (pinfunction "XXX_3") (pintype "passive"))
    )
    (net (code "42") (name "/ROW_D") (class "Default")
      (node (ref "DD2") (pin "56") (pinfunction "PB4_56") (pintype "passive"))
      (node (ref "X3") (pin "19") (pinfunction "XXX_19") (pintype "passive"))
    )
    (net (code "43") (name "/ROW_E") (class "Default")
      (node (ref "DD2") (pin "57") (pinfunction "PB5_57") (pintype "passive"))
      (node (ref "X3") (pin "20") (pinfunction "XXX_20") (pintype "passive"))
    )
    (net (code "44") (name "/ROW_F") (class "Default")
      (node (ref "DD2") (pin "10") (pinfunction "PC2_10") (pintype "passive"))
    )
    (net (code "45") (name "/SPI_MISO") (class "Default")
      (node (ref "DD2") (pin "35") (pinfunction "PB14_35") (pintype "passive"))
      (node (ref "X4") (pin "11") (pinfunction "XXX_11") (pintype "passive"))
    )
    (net (code "46") (name "/SPI_MOSI") (class "Default")
      (node (ref "C31") (pin "1") (pinfunction "1_1") (pintype "passive"))
      (node (ref "DD2") (pin "36") (pinfunction "PB15_36") (pintype "passive"))
      (node (ref "R33") (pin "1") (pinfunction "1_1") (pintype "passive"))
    )
    (net (code "47") (name "/SPI_NSS") (class "Default")
      (node (ref "C33") (pin "1") (pinfunction "1_1") (pintype "passive"))
      (node (ref "DD2") (pin "33") (pinfunction "PB12_33") (pintype "passive"))
      (node (ref "R35") (pin "1") (pinfunction "1_1") (pintype "passive"))
    )
    (net (code "48") (name "/SPI_SCK") (class "Default")
      (node (ref "C32") (pin "1") (pinfunction "1_1") (pintype "passive"))
      (node (ref "DD2") (pin "34") (pinfunction "PB13_34") (pintype "passive"))
      (node (ref "R34") (pin "1") (pinfunction "1_1") (pintype "passive"))
    )
    (net (code "49") (name "/SWD_CLK") (class "Default")
      (node (ref "DD2") (pin "49") (pinfunction "PA14_49") (pintype "passive"))
      (node (ref "X1") (pin "5") (pinfunction "5_5") (pintype "passive"))
    )
    (net (code "50") (name "/SWD_IO") (class "Default")
      (node (ref "DD2") (pin "46") (pinfunction "PA13_46") (pintype "passive"))
      (node (ref "X1") (pin "3") (pinfunction "3_3") (pintype "passive"))
    )
    (net (code "51") (name "/TIM1_CH1_") (class "Default")
      (node (ref "C6") (pin "1") (pinfunction "1_1") (pintype "passive"))
      (node (ref "DD2") (pin "41") (pinfunction "PA8_41") (pintype "passive"))
      (node (ref "R7") (pin "2") (pinfunction "2_2") (pintype "passive"))
    )
    (net (code "52") (name "/TIM1_CH1_RAW") (class "Default")
      (node (ref "ENC2") (pin "1") (pinfunction "CHA_1") (pintype "passive"))
      (node (ref "R7") (pin "1") (pinfunction "1_1") (pintype "passive"))
    )
    (net (code "53") (name "/TIM1_CH2_") (class "Default")
      (node (ref "C5") (pin "1") (pinfunction "1_1") (pintype "passive"))
      (node (ref "DD2") (pin "42") (pinfunction "PA9_42") (pintype "passive"))
      (node (ref "R9") (pin "2") (pinfunction "2_2") (pintype "passive"))
    )
    (net (code "54") (name "/TIM1_CH2_RAW") (class "Default")
      (node (ref "ENC2") (pin "3") (pinfunction "CHB_3") (pintype "passive"))
      (node (ref "R9") (pin "1") (pinfunction "1_1") (pintype "passive"))
    )
    (net (code "55") (name "/TIM2_CH1_") (class "Default")
      (node (ref "C4") (pin "1") (pinfunction "1_1") (pintype "passive"))
      (node (ref "DD2") (pin "14") (pinfunction "PA0_14") (pintype "passive"))
      (node (ref "R12") (pin "2") (pinfunction "2_2") (pintype "passive"))
    )
    (net (code "56") (name "/TIM2_CH1_RAW") (class "Default")
      (node (ref "ENC3") (pin "1") (pinfunction "CHA_1") (pintype "passive"))
      (node (ref "R12") (pin "1") (pinfunction "1_1") (pintype "passive"))
    )
    (net (code "57") (name "/TIM2_CH2_") (class "Default")
      (node (ref "C3") (pin "1") (pinfunction "1_1") (pintype "passive"))
      (node (ref "DD2") (pin "15") (pinfunction "PA1_15") (pintype "passive"))
      (node (ref "R14") (pin "2") (pinfunction "2_2") (pintype "passive"))
    )
    (net (code "58") (name "/TIM2_CH2_RAW") (class "Default")
      (node (ref "ENC3") (pin "3") (pinfunction "CHB_3") (pintype "passive"))
      (node (ref "R14") (pin "1") (pinfunction "1_1") (pintype "passive"))
    )
    (net (code "59") (name "/TIM3_CH1_") (class "Default")
      (node (ref "C8") (pin "1") (pinfunction "1_1") (pintype "passive"))
      (node (ref "DD2") (pin "37") (pinfunction "PC6_37") (pintype "passive"))
      (node (ref "R3") (pin "2") (pinfunction "2_2") (pintype "passive"))
    )
    (net (code "60") (name "/TIM3_CH1_RAW") (class "Default")
      (node (ref "ENC1") (pin "1") (pinfunction "CHA_1") (pintype "passive"))
      (node (ref "R3") (pin "1") (pinfunction "1_1") (pintype "passive"))
    )
    (net (code "61") (name "/TIM3_CH2_") (class "Default")
      (node (ref "C7") (pin "1") (pinfunction "1_1") (pintype "passive"))
      (node (ref "DD2") (pin "38") (pinfunction "PC7_38") (pintype "passive"))
      (node (ref "R5") (pin "2") (pinfunction "2_2") (pintype "passive"))
    )
    (net (code "62") (name "/TIM3_CH2_RAW") (class "Default")
      (node (ref "ENC1") (pin "3") (pinfunction "CHB_3") (pintype "passive"))
      (node (ref "R5") (pin "1") (pinfunction "1_1") (pintype "passive"))
    )
    (net (code "63") (name "GND") (class "Default")
      (node (ref "1") (pin "2") (pinfunction "2_2") (pintype "passive"))
      (node (ref "2") (pin "2") (pinfunction "2_2") (pintype "passive"))
      (node (ref "3") (pin "2") (pinfunction "2_2") (pintype "passive"))
      (node (ref "C1") (pin "1") (pinfunction "1_1") (pintype "passive"))
      (node (ref "C10") (pin "2") (pinfunction "2_2") (pintype "passive"))
      (node (ref "C11") (pin "2") (pinfunction "2_2") (pintype "passive"))
      (node (ref "C12") (pin "2") (pinfunction "2_2") (pintype "passive"))
      (node (ref "C13") (pin "2") (pinfunction "2_2") (pintype "passive"))
      (node (ref "C14") (pin "2") (pinfunction "2_2") (pintype "passive"))
      (node (ref "C15") (pin "2") (pinfunction "2_2") (pintype "passive"))
      (node (ref "C16") (pin "2") (pinfunction "2_2") (pintype "passive"))
      (node (ref "C17") (pin "1") (pinfunction "1_1") (pintype "passive"))
      (node (ref "C18") (pin "1") (pinfunction "1_1") (pintype "passive"))
      (node (ref "C2") (pin "1") (pinfunction "1_1") (pintype "passive"))
      (node (ref "C21") (pin "1") (pinfunction "1_1") (pintype "passive"))
      (node (ref "C22") (pin "1") (pinfunction "1_1") (pintype "passive"))
      (node (ref "C23") (pin "1") (pinfunction "1_1") (pintype "passive"))
      (node (ref "C24") (pin "1") (pinfunction "1_1") (pintype "passive"))
      (node (ref "C25") (pin "1") (pinfunction "1_1") (pintype "passive"))
      (node (ref "C26") (pin "2") (pinfunction "2_2") (pintype "passive"))
      (node (ref "C27") (pin "2") (pinfunction "2_2") (pintype "passive"))
      (node (ref "C28") (pin "2") (pinfunction "2_2") (pintype "passive"))
      (node (ref "C29") (pin "2") (pinfunction "2_2") (pintype "passive"))
      (node (ref "C3") (pin "2") (pinfunction "2_2") (pintype "passive"))
      (node (ref "C30") (pin "2") (pinfunction "2_2") (pintype "passive"))
      (node (ref "C31") (pin "2") (pinfunction "2_2") (pintype "passive"))
      (node (ref "C32") (pin "2") (pinfunction "2_2") (pintype "passive"))
      (node (ref "C33") (pin "2") (pinfunction "2_2") (pintype "passive"))
      (node (ref "C4") (pin "2") (pinfunction "2_2") (pintype "passive"))
      (node (ref "C5") (pin "2") (pinfunction "2_2") (pintype "passive"))
      (node (ref "C6") (pin "2") (pinfunction "2_2") (pintype "passive"))
      (node (ref "C7") (pin "2") (pinfunction "2_2") (pintype "passive"))
      (node (ref "C8") (pin "2") (pinfunction "2_2") (pintype "passive"))
      (node (ref "C9") (pin "1") (pinfunction "1_1") (pintype "passive"))
      (node (ref "DD1") (pin "5") (pinfunction "GND_5") (pintype "passive"))
      (node (ref "DD2") (pin "12") (pinfunction "VSSA_12") (pintype "power_in"))
      (node (ref "DD2") (pin "18") (pinfunction "VSS_18") (pintype "power_in"))
      (node (ref "DD2") (pin "31") (pinfunction "VSS_31") (pintype "power_in"))
      (node (ref "DD2") (pin "47") (pinfunction "VSS_47") (pintype "power_in"))
      (node (ref "DD2") (pin "63") (pinfunction "VSS_63") (pintype "power_in"))
      (node (ref "ENC1") (pin "2") (pinfunction "COM_2") (pintype "passive"))
      (node (ref "ENC2") (pin "2") (pinfunction "COM_2") (pintype "passive"))
      (node (ref "ENC3") (pin "2") (pinfunction "COM_2") (pintype "passive"))
      (node (ref "J1") (pin "1") (pinfunction "1_1") (pintype "passive"))
      (node (ref "R1") (pin "3") (pinfunction "3_3") (pintype "passive"))
      (node (ref "R11") (pin "3") (pinfunction "3_3") (pintype "passive"))
      (node (ref "R16") (pin "3") (pinfunction "3_3") (pintype "passive"))
      (node (ref "R17") (pin "3") (pinfunction "3_3") (pintype "passive"))
      (node (ref "R18") (pin "3") (pinfunction "3_3") (pintype "passive"))
      (node (ref "R19") (pin "3") (pinfunction "3_3") (pintype "passive"))
      (node (ref "R20") (pin "1") (pinfunction "1_1") (pintype "passive"))
      (node (ref "R21") (pin "3") (pinfunction "3_3") (pintype "passive"))
      (node (ref "R22") (pin "1") (pinfunction "1_1") (pintype "passive"))
      (node (ref "R23") (pin "1") (pinfunction "1_1") (pintype "passive"))
      (node (ref "R32") (pin "2") (pinfunction "2_2") (pintype "passive"))
      (node (ref "VT1") (pin "2") (pinfunction "E_2") (pintype "passive"))
      (node (ref "VT2") (pin "2") (pinfunction "E_2") (pintype "passive"))
      (node (ref "VT3") (pin "2") (pinfunction "E_2") (pintype "passive"))
      (node (ref "VT4") (pin "2") (pinfunction "E_2") (pintype "passive"))
      (node (ref "VT5") (pin "2") (pinfunction "E_2") (pintype "passive"))
      (node (ref "VT6") (pin "2") (pinfunction "E_2") (pintype "passive"))
      (node (ref "X1") (pin "2") (pinfunction "2_2") (pintype "passive"))
      (node (ref "X1") (pin "4") (pinfunction "4_4") (pintype "passive"))
      (node (ref "X1") (pin "6") (pinfunction "6_6") (pintype "passive"))
      (node (ref "X1") (pin "8") (pinfunction "8_8") (pintype "passive"))
      (node (ref "X4") (pin "10") (pinfunction "XXX_10") (pintype "passive"))
      (node (ref "X4") (pin "12") (pinfunction "XXX_12") (pintype "passive"))
      (node (ref "X4") (pin "14") (pinfunction "XXX_14") (pintype "passive"))
      (node (ref "X4") (pin "16") (pinfunction "XXX_16") (pintype "passive"))
      (node (ref "X4") (pin "18") (pinfunction "XXX_18") (pintype "passive"))
      (node (ref "X4") (pin "20") (pinfunction "XXX_20") (pintype "passive"))
      (node (ref "X4") (pin "8") (pinfunction "XXX_8") (pintype "passive"))
    )
    (net (code "64") (name "Net-(C19-Pad1)") (class "Default")
      (node (ref "C19") (pin "1") (pinfunction "1_1") (pintype "passive"))
      (node (ref "R24") (pin "2") (pinfunction "2_2") (pintype "passive"))
    )
    (net (code "65") (name "Net-(DD1-FPWMO)") (class "Default")
      (node (ref "DD1") (pin "3") (pinfunction "FPWMO_3") (pintype "passive"))
      (node (ref "R22") (pin "2") (pinfunction "2_2") (pintype "passive"))
    )
    (net (code "66") (name "Net-(DD1-FSW)") (class "Default")
      (node (ref "DD1") (pin "2") (pinfunction "FSW_2") (pintype "passive"))
      (node (ref "R20") (pin "2") (pinfunction "2_2") (pintype "passive"))
    )
    (net (code "67") (name "Net-(DD1-ISET)") (class "Default")
      (node (ref "DD1") (pin "11") (pinfunction "ISET_11") (pintype "passive"))
      (node (ref "R23") (pin "2") (pinfunction "2_2") (pintype "passive"))
    )
    (net (code "68") (name "Net-(DD1-MODE)") (class "Default")
      (node (ref "DD1") (pin "22") (pinfunction "MODE_22") (pintype "passive"))
      (node (ref "J1") (pin "2") (pinfunction "2_2") (pintype "passive"))
    )
    (net (code "69") (name "Net-(DD1-OVP)") (class "Default")
      (node (ref "DD1") (pin "16") (pinfunction "OVP_16") (pintype "passive"))
      (node (ref "R24") (pin "1") (pinfunction "1_1") (pintype "passive"))
      (node (ref "R25") (pin "1") (pinfunction "1_1") (pintype "passive"))
    )
    (net (code "70") (name "Net-(DD1-SW1)") (class "Default")
      (node (ref "DD1") (pin "19") (pinfunction "SW2_19") (pintype "passive"))
      (node (ref "DD1") (pin "20") (pinfunction "SW1_20") (pintype "passive"))
      (node (ref "L1") (pin "2") (pinfunction "2_2") (pintype "passive"))
      (node (ref "VD1") (pin "1") (pinfunction "anode_1") (pintype "passive"))
    )
    (net (code "71") (name "Net-(DD1-VDD)") (class "Default")
      (node (ref "C22") (pin "2") (pinfunction "2_2") (pintype "passive"))
      (node (ref "DD1") (pin "24") (pinfunction "VDD_24") (pintype "passive"))
    )
    (net (code "72") (name "Net-(DD2-BOOT)") (class "Default")
      (node (ref "DD2") (pin "60") (pinfunction "BOOT_60") (pintype "passive"))
      (node (ref "R32") (pin "1") (pinfunction "1_1") (pintype "passive"))
    )
    (net (code "73") (name "Net-(R33-Pad2)") (class "Default")
      (node (ref "R33") (pin "2") (pinfunction "2_2") (pintype "passive"))
      (node (ref "X4") (pin "9") (pinfunction "XXX_9") (pintype "passive"))
    )
    (net (code "74") (name "Net-(R34-Pad2)") (class "Default")
      (node (ref "R34") (pin "2") (pinfunction "2_2") (pintype "passive"))
      (node (ref "X4") (pin "13") (pinfunction "XXX_13") (pintype "passive"))
    )
    (net (code "75") (name "Net-(R35-Pad2)") (class "Default")
      (node (ref "R35") (pin "2") (pinfunction "2_2") (pintype "passive"))
      (node (ref "X4") (pin "15") (pinfunction "XXX_15") (pintype "passive"))
    )
    (net (code "76") (name "Net-(R36-Pad2)") (class "Default")
      (node (ref "R36") (pin "2") (pinfunction "2_2") (pintype "passive"))
      (node (ref "X3") (pin "10") (pinfunction "XXX_10") (pintype "passive"))
    )
    (net (code "77") (name "Net-(R37-Pad2)") (class "Default")
      (node (ref "R37") (pin "2") (pinfunction "2_2") (pintype "passive"))
      (node (ref "X3") (pin "11") (pinfunction "XXX_11") (pintype "passive"))
    )
    (net (code "78") (name "Net-(R38-Pad2)") (class "Default")
      (node (ref "R38") (pin "2") (pinfunction "2_2") (pintype "passive"))
      (node (ref "X3") (pin "12") (pinfunction "XXX_12") (pintype "passive"))
    )
    (net (code "79") (name "Net-(R39-Pad2)") (class "Default")
      (node (ref "R39") (pin "2") (pinfunction "2_2") (pintype "passive"))
      (node (ref "X3") (pin "13") (pinfunction "XXX_13") (pintype "passive"))
    )
    (net (code "80") (name "Net-(R40-Pad2)") (class "Default")
      (node (ref "R40") (pin "2") (pinfunction "2_2") (pintype "passive"))
      (node (ref "X3") (pin "14") (pinfunction "XXX_14") (pintype "passive"))
    )
    (net (code "81") (name "Net-(R41-Pad2)") (class "Default")
      (node (ref "R41") (pin "2") (pinfunction "2_2") (pintype "passive"))
      (node (ref "X3") (pin "15") (pinfunction "XXX_15") (pintype "passive"))
    )
    (net (code "82") (name "Net-(VD1-cathode)") (class "Default")
      (node (ref "VD1") (pin "2") (pinfunction "cathode_2") (pintype "passive"))
      (node (ref "X2") (pin "10") (pinfunction "XXX_10") (pintype "passive"))
      (node (ref "X2") (pin "11") (pinfunction "XXX_11") (pintype "passive"))
      (node (ref "X2") (pin "8") (pinfunction "XXX_8") (pintype "passive"))
      (node (ref "X2") (pin "9") (pinfunction "XXX_9") (pintype "passive"))
    )
    (net (code "83") (name "Net-(VT1-B)") (class "Default")
      (node (ref "R42") (pin "2") (pinfunction "2_2") (pintype "passive"))
      (node (ref "VT1") (pin "1") (pinfunction "B_1") (pintype "passive"))
    )
    (net (code "84") (name "Net-(VT1-C)") (class "Default")
      (node (ref "R36") (pin "1") (pinfunction "1_1") (pintype "passive"))
      (node (ref "VT1") (pin "3") (pinfunction "C_3") (pintype "passive"))
    )
    (net (code "85") (name "Net-(VT2-B)") (class "Default")
      (node (ref "R43") (pin "2") (pinfunction "2_2") (pintype "passive"))
      (node (ref "VT2") (pin "1") (pinfunction "B_1") (pintype "passive"))
    )
    (net (code "86") (name "Net-(VT2-C)") (class "Default")
      (node (ref "R37") (pin "1") (pinfunction "1_1") (pintype "passive"))
      (node (ref "VT2") (pin "3") (pinfunction "C_3") (pintype "passive"))
    )
    (net (code "87") (name "Net-(VT3-B)") (class "Default")
      (node (ref "R44") (pin "2") (pinfunction "2_2") (pintype "passive"))
      (node (ref "VT3") (pin "1") (pinfunction "B_1") (pintype "passive"))
    )
    (net (code "88") (name "Net-(VT3-C)") (class "Default")
      (node (ref "R38") (pin "1") (pinfunction "1_1") (pintype "passive"))
      (node (ref "VT3") (pin "3") (pinfunction "C_3") (pintype "passive"))
    )
    (net (code "89") (name "Net-(VT4-B)") (class "Default")
      (node (ref "R45") (pin "2") (pinfunction "2_2") (pintype "passive"))
      (node (ref "VT4") (pin "1") (pinfunction "B_1") (pintype "passive"))
    )
    (net (code "90") (name "Net-(VT4-C)") (class "Default")
      (node (ref "R39") (pin "1") (pinfunction "1_1") (pintype "passive"))
      (node (ref "VT4") (pin "3") (pinfunction "C_3") (pintype "passive"))
    )
    (net (code "91") (name "Net-(VT5-B)") (class "Default")
      (node (ref "R46") (pin "2") (pinfunction "2_2") (pintype "passive"))
      (node (ref "VT5") (pin "1") (pinfunction "B_1") (pintype "passive"))
    )
    (net (code "92") (name "Net-(VT5-C)") (class "Default")
      (node (ref "R40") (pin "1") (pinfunction "1_1") (pintype "passive"))
      (node (ref "VT5") (pin "3") (pinfunction "C_3") (pintype "passive"))
    )
    (net (code "93") (name "Net-(VT6-B)") (class "Default")
      (node (ref "R47") (pin "2") (pinfunction "2_2") (pintype "passive"))
      (node (ref "VT6") (pin "1") (pinfunction "B_1") (pintype "passive"))
    )
    (net (code "94") (name "Net-(VT6-C)") (class "Default")
      (node (ref "R41") (pin "1") (pinfunction "1_1") (pintype "passive"))
      (node (ref "VT6") (pin "3") (pinfunction "C_3") (pintype "passive"))
    )
    (net (code "95") (name "PWR_GND") (class "Default")
      (node (ref "1") (pin "1") (pinfunction "1_1") (pintype "passive"))
      (node (ref "2") (pin "1") (pinfunction "1_1") (pintype "passive"))
      (node (ref "3") (pin "1") (pinfunction "1_1") (pintype "passive"))
      (node (ref "C19") (pin "2") (pinfunction "2_2") (pintype "passive"))
      (node (ref "C20") (pin "1") (pinfunction "1_1") (pintype "passive"))
      (node (ref "DD1") (pin "17") (pinfunction "PGND2_17") (pintype "passive"))
      (node (ref "DD1") (pin "18") (pinfunction "PGND1_18") (pintype "passive"))
      (node (ref "R25") (pin "2") (pinfunction "2_2") (pintype "passive"))
      (node (ref "X5") (pin "3") (pinfunction "XXX_3") (pintype "passive"))
    )
    (net (code "96") (name "VCC3.3V") (class "Default")
      (node (ref "C1") (pin "2") (pinfunction "2_2") (pintype "passive"))
      (node (ref "C17") (pin "2") (pinfunction "2_2") (pintype "passive"))
      (node (ref "C18") (pin "2") (pinfunction "2_2") (pintype "passive"))
      (node (ref "C2") (pin "2") (pinfunction "2_2") (pintype "passive"))
      (node (ref "C21") (pin "2") (pinfunction "2_2") (pintype "passive"))
      (node (ref "C23") (pin "2") (pinfunction "2_2") (pintype "passive"))
      (node (ref "C26") (pin "1") (pinfunction "1_1") (pintype "passive"))
      (node (ref "C27") (pin "1") (pinfunction "1_1") (pintype "passive"))
      (node (ref "C28") (pin "1") (pinfunction "1_1") (pintype "passive"))
      (node (ref "C29") (pin "1") (pinfunction "1_1") (pintype "passive"))
      (node (ref "C30") (pin "1") (pinfunction "1_1") (pintype "passive"))
      (node (ref "C9") (pin "2") (pinfunction "2_2") (pintype "passive"))
      (node (ref "DD2") (pin "1") (pinfunction "VBAT_1") (pintype "power_in"))
      (node (ref "DD2") (pin "13") (pinfunction "VDDA_13") (pintype "power_in"))
      (node (ref "DD2") (pin "19") (pinfunction "VDD_19") (pintype "power_in"))
      (node (ref "DD2") (pin "32") (pinfunction "VDD_32") (pintype "power_in"))
      (node (ref "DD2") (pin "48") (pinfunction "VDDIO2_48") (pintype "power_in"))
      (node (ref "DD2") (pin "64") (pinfunction "VDD_64") (pintype "power_in"))
      (node (ref "R1") (pin "1") (pinfunction "1_1") (pintype "passive"))
      (node (ref "R11") (pin "1") (pinfunction "1_1") (pintype "passive"))
      (node (ref "R16") (pin "1") (pinfunction "1_1") (pintype "passive"))
      (node (ref "R17") (pin "1") (pinfunction "1_1") (pintype "passive"))
      (node (ref "R18") (pin "1") (pinfunction "1_1") (pintype "passive"))
      (node (ref "R19") (pin "1") (pinfunction "1_1") (pintype "passive"))
      (node (ref "R21") (pin "1") (pinfunction "1_1") (pintype "passive"))
      (node (ref "R26") (pin "2") (pinfunction "2_2") (pintype "passive"))
      (node (ref "R27") (pin "2") (pinfunction "2_2") (pintype "passive"))
      (node (ref "R28") (pin "2") (pinfunction "2_2") (pintype "passive"))
      (node (ref "R29") (pin "2") (pinfunction "2_2") (pintype "passive"))
      (node (ref "R30") (pin "2") (pinfunction "2_2") (pintype "passive"))
      (node (ref "R31") (pin "2") (pinfunction "2_2") (pintype "passive"))
      (node (ref "X1") (pin "10") (pinfunction "10_10") (pintype "passive"))
      (node (ref "X4") (pin "1") (pinfunction "XXX_1") (pintype "passive"))
      (node (ref "X4") (pin "2") (pinfunction "XXX_2") (pintype "passive"))
      (node (ref "X4") (pin "3") (pinfunction "XXX_3") (pintype "passive"))
      (node (ref "X4") (pin "4") (pinfunction "XXX_4") (pintype "passive"))
      (node (ref "X4") (pin "5") (pinfunction "XXX_5") (pintype "passive"))
      (node (ref "X4") (pin "6") (pinfunction "XXX_6") (pintype "passive"))
    )
    (net (code "97") (name "VCC5V") (class "Default")
      (node (ref "C20") (pin "2") (pinfunction "2_2") (pintype "passive"))
      (node (ref "C24") (pin "2") (pinfunction "2_2") (pintype "passive"))
      (node (ref "DD1") (pin "23") (pinfunction "VIN_23") (pintype "passive"))
      (node (ref "L1") (pin "1") (pinfunction "1_1") (pintype "passive"))
      (node (ref "X3") (pin "4") (pinfunction "XXX_4") (pintype "passive"))
      (node (ref "X3") (pin "5") (pinfunction "XXX_5") (pintype "passive"))
      (node (ref "X3") (pin "6") (pinfunction "XXX_6") (pintype "passive"))
      (node (ref "X5") (pin "1") (pinfunction "XXX_1") (pintype "passive"))
    )
    (net (code "98") (name "unconnected-(DD1-FAULT-Pad21)") (class "Default")
      (node (ref "DD1") (pin "21") (pinfunction "FAULT_21") (pintype "passive"))
    )
    (net (code "99") (name "unconnected-(DD1-IFB1-Pad15)") (class "Default")
      (node (ref "DD1") (pin "15") (pinfunction "IFB1_15") (pintype "passive"))
    )
    (net (code "100") (name "unconnected-(DD1-IFB8-Pad7)") (class "Default")
      (node (ref "DD1") (pin "7") (pinfunction "IFB8_7") (pintype "passive"))
    )
    (net (code "101") (name "unconnected-(DD1-NC-Pad4)") (class "Default")
      (node (ref "DD1") (pin "4") (pinfunction "NC_4") (pintype "passive"))
    )
    (net (code "102") (name "unconnected-(DD2-PA10-Pad43)") (class "Default")
      (node (ref "DD2") (pin "43") (pinfunction "PA10_43") (pintype "passive"))
    )
    (net (code "103") (name "unconnected-(DD2-PB2-Pad28)") (class "Default")
      (node (ref "DD2") (pin "28") (pinfunction "PB2_28") (pintype "passive"))
    )
    (net (code "104") (name "unconnected-(DD2-PB6-Pad58)") (class "Default")
      (node (ref "DD2") (pin "58") (pinfunction "PB6_58") (pintype "passive"))
    )
    (net (code "105") (name "unconnected-(DD2-PB7-Pad59)") (class "Default")
      (node (ref "DD2") (pin "59") (pinfunction "PB7_59") (pintype "passive"))
    )
    (net (code "106") (name "unconnected-(DD2-PB10-Pad29)") (class "Default")
      (node (ref "DD2") (pin "29") (pinfunction "PB10_29") (pintype "passive"))
    )
    (net (code "107") (name "unconnected-(DD2-PB11-Pad30)") (class "Default")
      (node (ref "DD2") (pin "30") (pinfunction "PB11_30") (pintype "passive"))
    )
    (net (code "108") (name "unconnected-(DD2-PC8-Pad39)") (class "Default")
      (node (ref "DD2") (pin "39") (pinfunction "PC8_39") (pintype "passive"))
    )
    (net (code "109") (name "unconnected-(DD2-PC9-Pad40)") (class "Default")
      (node (ref "DD2") (pin "40") (pinfunction "PC9_40") (pintype "passive"))
    )
    (net (code "110") (name "unconnected-(DD2-PF1{slash}X_O-Pad6)") (class "Default")
      (node (ref "DD2") (pin "6") (pinfunction "PF1/X_O_6") (pintype "passive"))
    )
    (net (code "111") (name "unconnected-(X1-Pad7)") (class "Default")
      (node (ref "X1") (pin "7") (pinfunction "7_7") (pintype "passive"))
    )
    (net (code "112") (name "unconnected-(X1-Pad9)") (class "Default")
      (node (ref "X1") (pin "9") (pinfunction "9_9") (pintype "passive"))
    )
    (net (code "113") (name "unconnected-(X2-XXX-Pad7)") (class "Default")
      (node (ref "X2") (pin "7") (pinfunction "XXX_7") (pintype "passive"))
    )
    (net (code "114") (name "unconnected-(X2-XXX-Pad12)") (class "Default")
      (node (ref "X2") (pin "12") (pinfunction "XXX_12") (pintype "passive"))
    )
    (net (code "115") (name "unconnected-(X4-XXX-Pad7)") (class "Default")
      (node (ref "X4") (pin "7") (pinfunction "XXX_7") (pintype "passive"))
    )
    (net (code "116") (name "unconnected-(X4-XXX-Pad17)") (class "Default")
      (node (ref "X4") (pin "17") (pinfunction "XXX_17") (pintype "passive"))
    )
    (net (code "117") (name "unconnected-(X4-XXX-Pad19)") (class "Default")
      (node (ref "X4") (pin "19") (pinfunction "XXX_19") (pintype "passive"))
    )
    (net (code "118") (name "unconnected-(X5-XXX-Pad2)") (class "Default")
      (node (ref "X5") (pin "2") (pinfunction "XXX_2") (pintype "passive"))
    )
  )
)
